# Top.net
KiCad netlist of a schematic drawn in Altium Designer
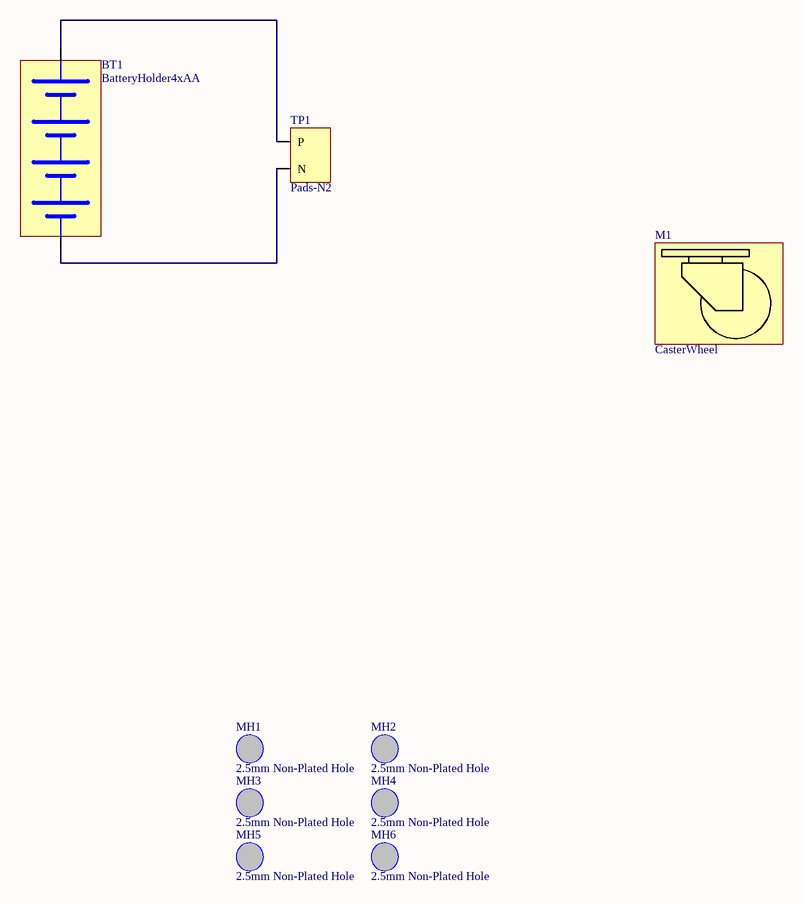
[diagram p0: Top.SchDoc]

(export (version "E")
  (design (tool "Eeschema 10.0.6"))
  (components
    (comp (ref "BT1")
      (value "BatteryHolder4xAA")
      (footprint "BATTERY_HOLDER_4AA")
      (libsource (lib "Common") (part "BatteryHolder4xAA"))
    )
    (comp (ref "M1")
      (value "CasterWheel")
      (footprint "CASTER_WHEEL")
      (libsource (lib "Common") (part "CasterWheel"))
    )
    (comp (ref "MH1")
      (value "2.5mm Non-Plated Hole")
      (footprint "MTG250X550")
      (libsource (lib "library") (part "HOLE_UNPLATED"))
    )
    (comp (ref "MH2")
      (value "2.5mm Non-Plated Hole")
      (footprint "MTG250X550")
      (libsource (lib "library") (part "HOLE_UNPLATED"))
    )
    (comp (ref "MH3")
      (value "2.5mm Non-Plated Hole")
      (footprint "MTG250X550")
      (libsource (lib "library") (part "HOLE_UNPLATED"))
    )
    (comp (ref "MH4")
      (value "2.5mm Non-Plated Hole")
      (footprint "MTG250X550")
      (libsource (lib "library") (part "HOLE_UNPLATED"))
    )
    (comp (ref "MH5")
      (value "2.5mm Non-Plated Hole")
      (footprint "MTG250X550")
      (libsource (lib "library") (part "HOLE_UNPLATED"))
    )
    (comp (ref "MH6")
      (value "2.5mm Non-Plated Hole")
      (footprint "MTG250X550")
      (libsource (lib "library") (part "HOLE_UNPLATED"))
    )
    (comp (ref "TP1") (value "Pads-N2") (footprint "PADS-N2") (libsource (lib "Common") (part "Pads-N2")))
  )
  (nets
    (net (code "1") (name "Net-(BT1-+)") (class "Default")
      (node (ref "BT1") (pin "1") (pinfunction "+_1") (pintype "passive"))
      (node (ref "TP1") (pin "2") (pinfunction "P_2") (pintype "passive"))
    )
    (net (code "2") (name "Net-(BT1--)") (class "Default")
      (node (ref "BT1") (pin "2") (pinfunction "-_2") (pintype "passive"))
      (node (ref "TP1") (pin "1") (pinfunction "N_1") (pintype "passive"))
    )
  )
)
